# connector.net
KiCad netlist of a schematic drawn in Altium Designer
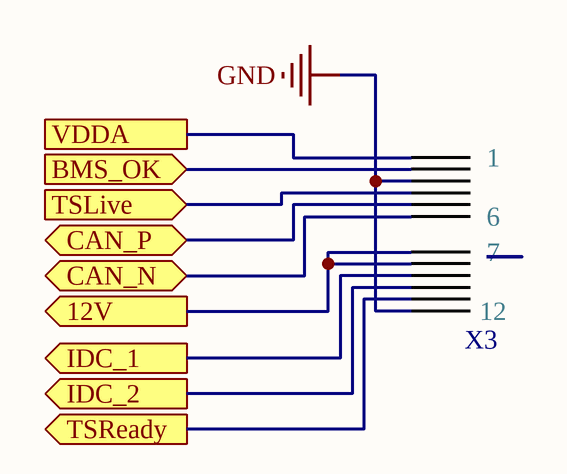
[diagram p0: connector.SchDoc]

(export (version "E")
  (design (tool "Eeschema 10.0.6"))
  (components
    (comp (ref "X3")
      (value "4-794619-2")
      (footprint "4-794619-2")
      (description "12p te")
      (libsource (lib "altlib") (part "4-794619-2"))
    )
  )
  (nets
    (net (code "1") (name "/12V") (class "Default")
      (node (ref "X3") (pin "7") (pintype "passive"))
      (node (ref "X3") (pin "8") (pintype "passive"))
    )
    (net (code "2") (name "/BMS_OK") (class "Default") (node (ref "X3") (pin "2") (pintype "passive")))
    (net (code "3") (name "/CAN_N") (class "Default") (node (ref "X3") (pin "6") (pintype "passive")))
    (net (code "4") (name "/CAN_P") (class "Default") (node (ref "X3") (pin "5") (pintype "passive")))
    (net (code "5") (name "/IDC_1") (class "Default") (node (ref "X3") (pin "9") (pintype "passive")))
    (net (code "6") (name "/IDC_2") (class "Default") (node (ref "X3") (pin "10") (pintype "passive")))
    (net (code "7") (name "/TSLive") (class "Default") (node (ref "X3") (pin "4") (pintype "passive")))
    (net (code "8") (name "/TSReady") (class "Default") (node (ref "X3") (pin "11") (pintype "passive")))
    (net (code "9") (name "/VDDA") (class "Default") (node (ref "X3") (pin "1") (pintype "passive")))
    (net (code "10") (name "GND") (class "Default")
      (node (ref "X3") (pin "12") (pinfunction "12_12") (pintype "passive"))
      (node (ref "X3") (pin "3") (pintype "passive"))
    )
  )
)
